# gnss.net
KiCad netlist of a schematic drawn in EAGLE
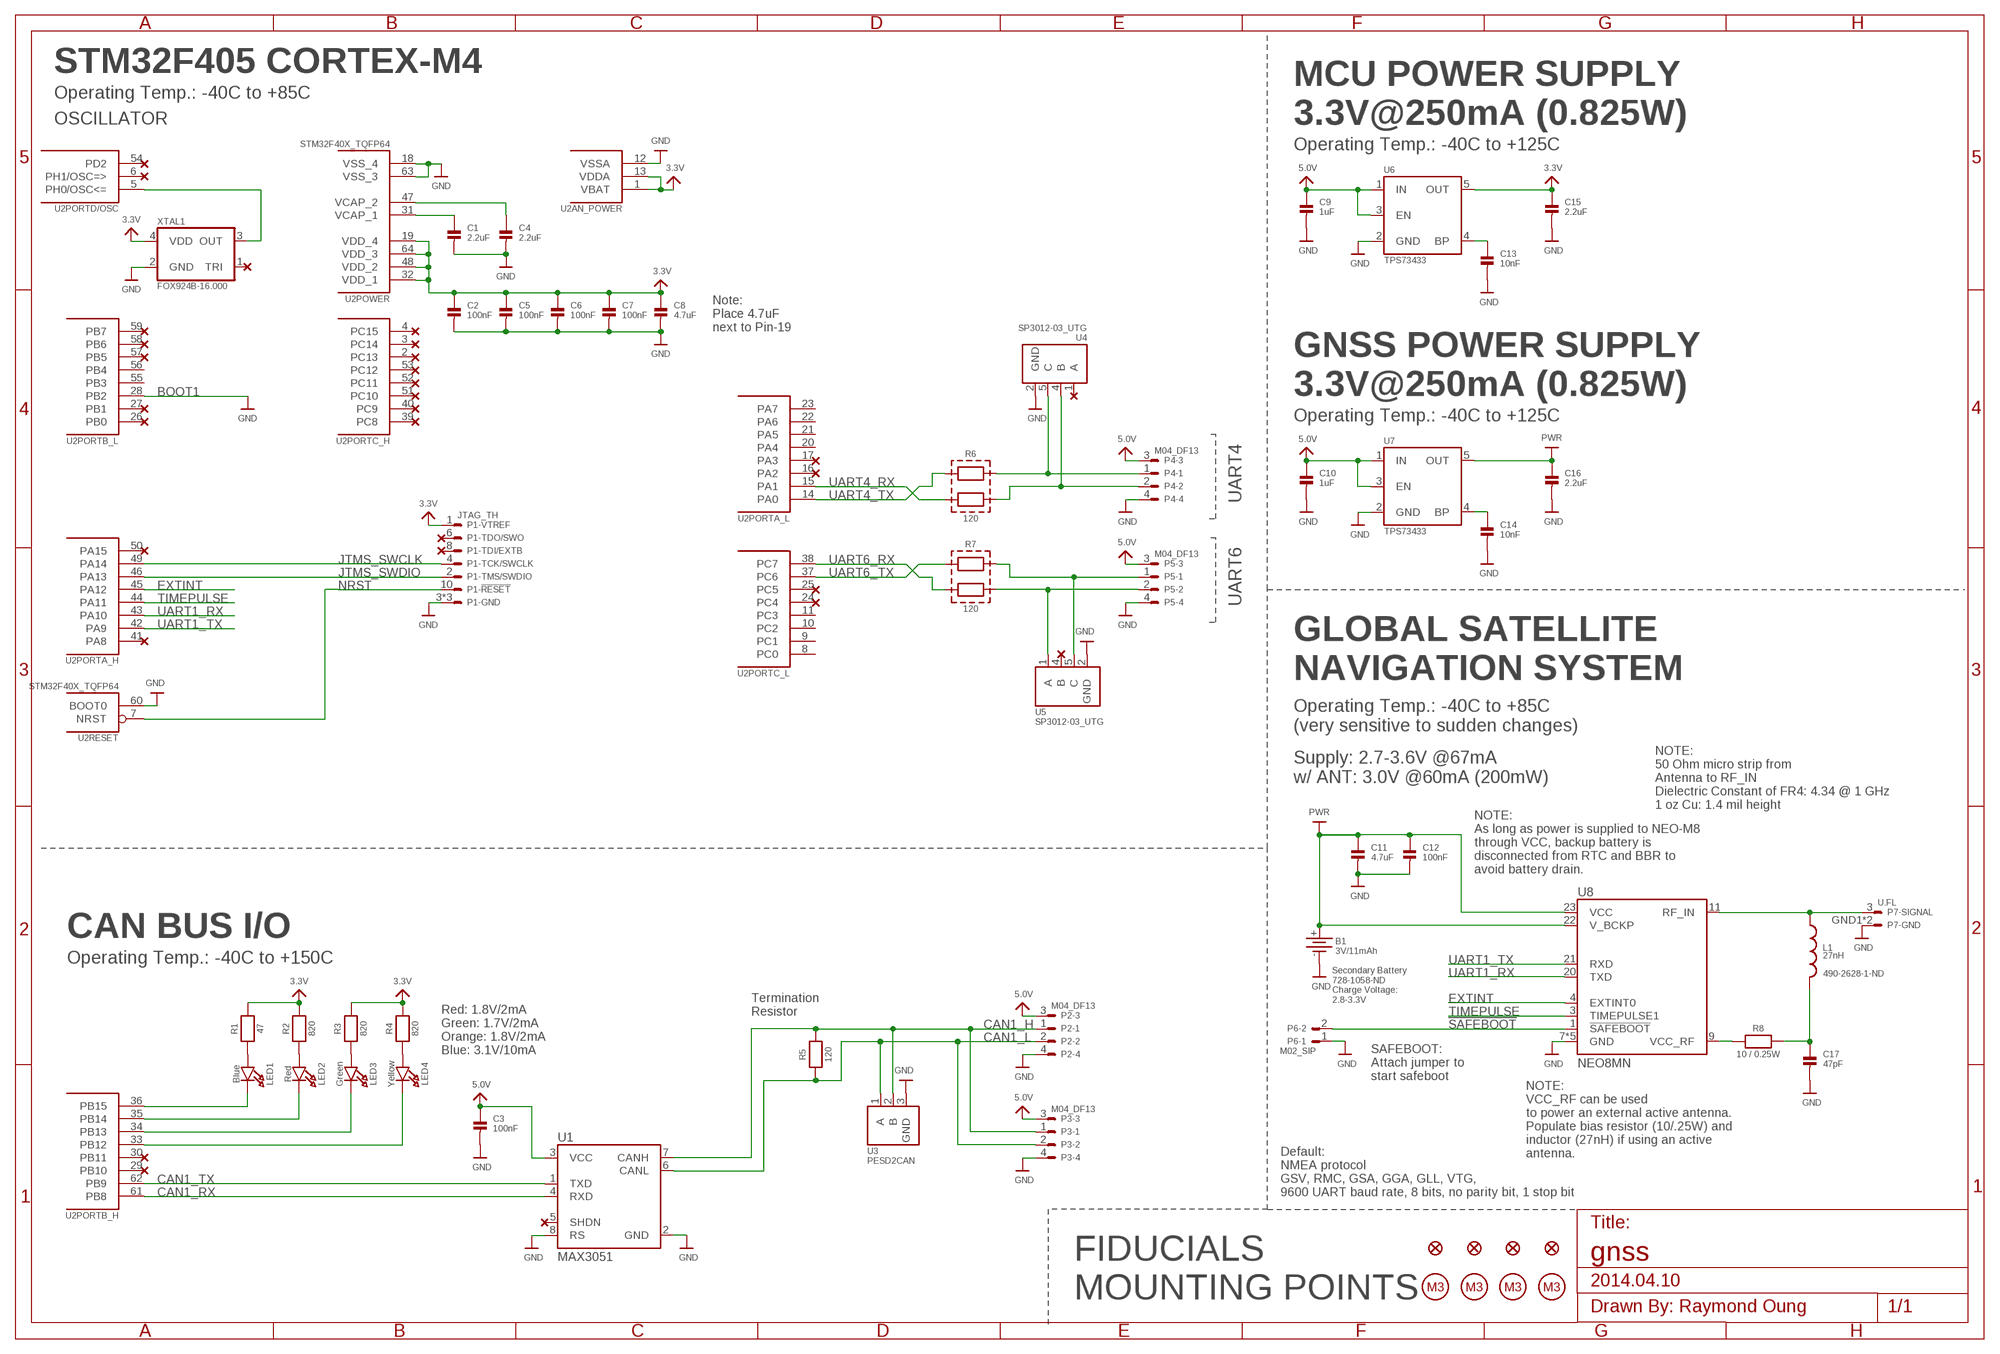
[diagram p0: schematic, sheet 1]

(export (version "E")
  (design (tool "Eeschema 10.0.6"))
  (components
    (comp (ref "B1")
      (value "3V/11mAh")
      (footprint "eagle-import:MS920SE")
      (libsource (lib "eagle-import") (part "BATTERY_MS920SE"))
    )
    (comp (ref "C1")
      (value "2.2uF")
      (footprint "eagle-import:0402")
      (libsource (lib "eagle-import") (part "CAP_CERAMIC0402"))
    )
    (comp (ref "C2")
      (value "100nF")
      (footprint "eagle-import:0402")
      (libsource (lib "eagle-import") (part "CAP_CERAMIC0402"))
    )
    (comp (ref "C3")
      (value "100nF")
      (footprint "eagle-import:0402")
      (libsource (lib "eagle-import") (part "CAP_CERAMIC0402"))
    )
    (comp (ref "C4")
      (value "2.2uF")
      (footprint "eagle-import:0402")
      (libsource (lib "eagle-import") (part "CAP_CERAMIC0402"))
    )
    (comp (ref "C5")
      (value "100nF")
      (footprint "eagle-import:0402")
      (libsource (lib "eagle-import") (part "CAP_CERAMIC0402"))
    )
    (comp (ref "C6")
      (value "100nF")
      (footprint "eagle-import:0402")
      (libsource (lib "eagle-import") (part "CAP_CERAMIC0402"))
    )
    (comp (ref "C7")
      (value "100nF")
      (footprint "eagle-import:0402")
      (libsource (lib "eagle-import") (part "CAP_CERAMIC0402"))
    )
    (comp (ref "C8")
      (value "4.7uF")
      (footprint "eagle-import:0402")
      (libsource (lib "eagle-import") (part "CAP_CERAMIC0402"))
    )
    (comp (ref "C9")
      (value "1uF")
      (footprint "eagle-import:0402")
      (libsource (lib "eagle-import") (part "CAP_CERAMIC0402"))
    )
    (comp (ref "C10")
      (value "1uF")
      (footprint "eagle-import:0402")
      (libsource (lib "eagle-import") (part "CAP_CERAMIC0402"))
    )
    (comp (ref "C11")
      (value "4.7uF")
      (footprint "eagle-import:0402")
      (libsource (lib "eagle-import") (part "CAP_CERAMIC0402"))
    )
    (comp (ref "C12")
      (value "100nF")
      (footprint "eagle-import:0402")
      (libsource (lib "eagle-import") (part "CAP_CERAMIC0402"))
    )
    (comp (ref "C13")
      (value "10nF")
      (footprint "eagle-import:0402")
      (libsource (lib "eagle-import") (part "CAP_CERAMIC0402"))
    )
    (comp (ref "C14")
      (value "10nF")
      (footprint "eagle-import:0402")
      (libsource (lib "eagle-import") (part "CAP_CERAMIC0402"))
    )
    (comp (ref "C15")
      (value "2.2uF")
      (footprint "eagle-import:0402")
      (libsource (lib "eagle-import") (part "CAP_CERAMIC0402"))
    )
    (comp (ref "C16")
      (value "2.2uF")
      (footprint "eagle-import:0402")
      (libsource (lib "eagle-import") (part "CAP_CERAMIC0402"))
    )
    (comp (ref "C17")
      (value "47pF")
      (footprint "eagle-import:0402")
      (libsource (lib "eagle-import") (part "CAP_CERAMIC0402"))
    )
    (comp (ref "L1")
      (value "27nH")
      (footprint "eagle-import:L0402")
      (libsource (lib "eagle-import") (part "INDUCTOR_0402"))
    )
    (comp (ref "LED1")
      (value "Blue")
      (footprint "eagle-import:CHIPLED_0603")
      (libsource (lib "eagle-import") (part "LED_0603"))
    )
    (comp (ref "LED2")
      (value "Red")
      (footprint "eagle-import:CHIPLED_0603")
      (libsource (lib "eagle-import") (part "LED_0603"))
    )
    (comp (ref "LED3")
      (value "Green")
      (footprint "eagle-import:CHIPLED_0603")
      (libsource (lib "eagle-import") (part "LED_0603"))
    )
    (comp (ref "LED4")
      (value "Yellow")
      (footprint "eagle-import:CHIPLED_0603")
      (libsource (lib "eagle-import") (part "LED_0603"))
    )
    (comp (ref "MP1")
      (value "M3")
      (footprint "eagle-import:MP_M3")
      (libsource (lib "eagle-import") (part "M3"))
    )
    (comp (ref "MP2")
      (value "M3")
      (footprint "eagle-import:MP_M3")
      (libsource (lib "eagle-import") (part "M3"))
    )
    (comp (ref "MP3")
      (value "M3")
      (footprint "eagle-import:MP_M3")
      (libsource (lib "eagle-import") (part "M3"))
    )
    (comp (ref "MP4")
      (value "M3")
      (footprint "eagle-import:MP_M3")
      (libsource (lib "eagle-import") (part "M3"))
    )
    (comp (ref "P1")
      (value "JTAG_TH")
      (footprint "eagle-import:FTSH-105-01-XXX-DV")
      (libsource (lib "eagle-import") (part "JTAG_TH"))
    )
    (comp (ref "P2")
      (value "M04_DF13")
      (footprint "eagle-import:DF13A-4P-1.25H")
      (libsource (lib "eagle-import") (part "M04_DF13"))
    )
    (comp (ref "P3")
      (value "M04_DF13")
      (footprint "eagle-import:DF13A-4P-1.25H")
      (libsource (lib "eagle-import") (part "M04_DF13"))
    )
    (comp (ref "P4")
      (value "M04_DF13")
      (footprint "eagle-import:DF13A-4P-1.25H")
      (libsource (lib "eagle-import") (part "M04_DF13"))
    )
    (comp (ref "P5")
      (value "M04_DF13")
      (footprint "eagle-import:DF13A-4P-1.25H")
      (libsource (lib "eagle-import") (part "M04_DF13"))
    )
    (comp (ref "P6")
      (value "M02_SIP")
      (footprint "eagle-import:1X02_LOCK")
      (libsource (lib "eagle-import") (part "M02_SIP"))
    )
    (comp (ref "P7")
      (value "U.FL")
      (footprint "eagle-import:U.FL")
      (libsource (lib "eagle-import") (part "U.FL"))
    )
    (comp (ref "R1")
      (value "47")
      (footprint "eagle-import:0402")
      (libsource (lib "eagle-import") (part "RESISTOR0402"))
    )
    (comp (ref "R2")
      (value "820")
      (footprint "eagle-import:0402")
      (libsource (lib "eagle-import") (part "RESISTOR0402"))
    )
    (comp (ref "R3")
      (value "820")
      (footprint "eagle-import:0402")
      (libsource (lib "eagle-import") (part "RESISTOR0402"))
    )
    (comp (ref "R4")
      (value "820")
      (footprint "eagle-import:0402")
      (libsource (lib "eagle-import") (part "RESISTOR0402"))
    )
    (comp (ref "R5")
      (value "120")
      (footprint "eagle-import:0603")
      (libsource (lib "eagle-import") (part "RESISTOR0603"))
    )
    (comp (ref "R6")
      (value "120")
      (footprint "eagle-import:EXBV4V")
      (libsource (lib "eagle-import") (part "RESISTOR2_0603X2"))
    )
    (comp (ref "R7")
      (value "120")
      (footprint "eagle-import:EXBV4V")
      (libsource (lib "eagle-import") (part "RESISTOR2_0603X2"))
    )
    (comp (ref "R8")
      (value "10 / 0.25W")
      (footprint "eagle-import:0603")
      (libsource (lib "eagle-import") (part "RESISTOR0603"))
    )
    (comp (ref "REF1")
      (value "FIDUCIAL1X2.5")
      (footprint "eagle-import:POINT-1MM")
      (libsource (lib "eagle-import") (part "FIDUCIAL1X2.5"))
    )
    (comp (ref "REF2")
      (value "FIDUCIAL1X2.5")
      (footprint "eagle-import:POINT-1MM")
      (libsource (lib "eagle-import") (part "FIDUCIAL1X2.5"))
    )
    (comp (ref "REF3")
      (value "FIDUCIAL1X2.5")
      (footprint "eagle-import:POINT-1MM")
      (libsource (lib "eagle-import") (part "FIDUCIAL1X2.5"))
    )
    (comp (ref "REF4")
      (value "FIDUCIAL1X2.5")
      (footprint "eagle-import:POINT-1MM")
      (libsource (lib "eagle-import") (part "FIDUCIAL1X2.5"))
    )
    (comp (ref "U1")
      (value "MAX3051")
      (footprint "eagle-import:SOT23-8")
      (libsource (lib "eagle-import") (part "MAX3051"))
    )
    (comp (ref "U2")
      (value "STM32F40X_TQFP64")
      (footprint "eagle-import:TQFP64")
      (libsource (lib "eagle-import") (part "STM32F40X_TQFP64"))
    )
    (comp (ref "U3")
      (value "PESD2CAN")
      (footprint "eagle-import:SOT23-3")
      (libsource (lib "eagle-import") (part "PESD2CAN"))
    )
    (comp (ref "U4")
      (value "SP3012-03_UTG")
      (footprint "eagle-import:UDFN06")
      (libsource (lib "eagle-import") (part "SP3012-03_UTG"))
    )
    (comp (ref "U5")
      (value "SP3012-03_UTG")
      (footprint "eagle-import:UDFN06")
      (libsource (lib "eagle-import") (part "SP3012-03_UTG"))
    )
    (comp (ref "U6")
      (value "TPS73433")
      (footprint "eagle-import:SOT23-5")
      (libsource (lib "eagle-import") (part "TPS73433"))
    )
    (comp (ref "U7")
      (value "TPS73433")
      (footprint "eagle-import:SOT23-5")
      (libsource (lib "eagle-import") (part "TPS73433"))
    )
    (comp (ref "U8")
      (value "NEO8MN")
      (footprint "eagle-import:NEOX")
      (libsource (lib "eagle-import") (part "NEO8MN"))
    )
    (comp (ref "XTAL1")
      (value "FOX924B-16.000")
      (footprint "eagle-import:OSCILLATOR-5.0X3.2A")
      (libsource (lib "eagle-import") (part "TCXO_5.0X3.2A"))
    )
  )
  (nets
    (net (code "1") (name "/CAN1_H") (class "Default")
      (node (ref "P2") (pin "1") (pinfunction "S_1") (pintype "passive"))
      (node (ref "P3") (pin "1") (pinfunction "S_1") (pintype "passive"))
      (node (ref "R5") (pin "2") (pinfunction "2_2") (pintype "passive"))
      (node (ref "U1") (pin "7") (pinfunction "CANH_7") (pintype "bidirectional"))
      (node (ref "U3") (pin "2") (pinfunction "B_2") (pintype "bidirectional"))
    )
    (net (code "2") (name "/CAN1_L") (class "Default")
      (node (ref "P2") (pin "2") (pinfunction "S_2") (pintype "passive"))
      (node (ref "P3") (pin "2") (pinfunction "S_2") (pintype "passive"))
      (node (ref "R5") (pin "1") (pinfunction "1_1") (pintype "passive"))
      (node (ref "U1") (pin "6") (pinfunction "CANL_6") (pintype "bidirectional"))
      (node (ref "U3") (pin "1") (pinfunction "A_1") (pintype "bidirectional"))
    )
    (net (code "3") (name "/CAN1_RX") (class "Default")
      (node (ref "U1") (pin "4") (pinfunction "RXD_4") (pintype "bidirectional"))
      (node (ref "U2") (pin "61") (pinfunction "PB8_61") (pintype "bidirectional"))
    )
    (net (code "4") (name "/CAN1_TX") (class "Default")
      (node (ref "U1") (pin "1") (pinfunction "TXD_1") (pintype "bidirectional"))
      (node (ref "U2") (pin "62") (pinfunction "PB9_62") (pintype "bidirectional"))
    )
    (net (code "5") (name "/EXTINT") (class "Default")
      (node (ref "U2") (pin "45") (pinfunction "PA12_45") (pintype "bidirectional"))
      (node (ref "U8") (pin "4") (pinfunction "EXTINT0_4") (pintype "bidirectional"))
    )
    (net (code "6") (name "/JTMS_SWCLK") (class "Default")
      (node (ref "P1") (pin "4") (pinfunction "S_4") (pintype "passive"))
      (node (ref "U2") (pin "49") (pinfunction "PA14_49") (pintype "bidirectional"))
    )
    (net (code "7") (name "/JTMS_SWDIO") (class "Default")
      (node (ref "P1") (pin "2") (pinfunction "S_2") (pintype "passive"))
      (node (ref "U2") (pin "46") (pinfunction "PA13_46") (pintype "bidirectional"))
    )
    (net (code "8") (name "/NRST") (class "Default")
      (node (ref "P1") (pin "10") (pinfunction "S_10") (pintype "passive"))
      (node (ref "U2") (pin "7") (pinfunction "NRST_7") (pintype "input"))
    )
    (net (code "9") (name "/TIMEPULSE") (class "Default")
      (node (ref "U2") (pin "44") (pinfunction "PA11_44") (pintype "bidirectional"))
      (node (ref "U8") (pin "3") (pinfunction "TIMEPULSE1_3") (pintype "bidirectional"))
    )
    (net (code "10") (name "/UART1_RX") (class "Default")
      (node (ref "U2") (pin "43") (pinfunction "PA10_43") (pintype "bidirectional"))
      (node (ref "U8") (pin "20") (pinfunction "TXD_20") (pintype "bidirectional"))
    )
    (net (code "11") (name "/UART1_TX") (class "Default")
      (node (ref "U2") (pin "42") (pinfunction "PA9_42") (pintype "bidirectional"))
      (node (ref "U8") (pin "21") (pinfunction "RXD_21") (pintype "bidirectional"))
    )
    (net (code "12") (name "/UART4_RX") (class "Default")
      (node (ref "R6") (pin "2") (pinfunction "2_2") (pintype "passive"))
      (node (ref "U2") (pin "15") (pinfunction "PA1_15") (pintype "bidirectional"))
    )
    (net (code "13") (name "/UART4_TX") (class "Default")
      (node (ref "R6") (pin "1") (pinfunction "1_1") (pintype "passive"))
      (node (ref "U2") (pin "14") (pinfunction "PA0_14") (pintype "bidirectional"))
    )
    (net (code "14") (name "/UART6_RX") (class "Default")
      (node (ref "R7") (pin "2") (pinfunction "2_2") (pintype "passive"))
      (node (ref "U2") (pin "38") (pinfunction "PC7_38") (pintype "bidirectional"))
    )
    (net (code "15") (name "/UART6_TX") (class "Default")
      (node (ref "R7") (pin "1") (pinfunction "1_1") (pintype "passive"))
      (node (ref "U2") (pin "37") (pinfunction "PC6_37") (pintype "bidirectional"))
    )
    (net (code "16") (name "/~{SAFEBOOT}") (class "Default")
      (node (ref "P6") (pin "2") (pinfunction "S_2") (pintype "passive"))
      (node (ref "U8") (pin "1") (pinfunction "~{SAFEBOOT}_1") (pintype "bidirectional"))
    )
    (net (code "17") (name "3.3V") (class "Default")
      (node (ref "C15") (pin "1") (pinfunction "P$1_1") (pintype "passive"))
      (node (ref "C2") (pin "1") (pinfunction "P$1_1") (pintype "passive"))
      (node (ref "C5") (pin "1") (pinfunction "P$1_1") (pintype "passive"))
      (node (ref "C6") (pin "1") (pinfunction "P$1_1") (pintype "passive"))
      (node (ref "C7") (pin "1") (pinfunction "P$1_1") (pintype "passive"))
      (node (ref "C8") (pin "1") (pinfunction "P$1_1") (pintype "passive"))
      (node (ref "P1") (pin "1") (pinfunction "S_1") (pintype "passive"))
      (node (ref "R1") (pin "2") (pinfunction "2_2") (pintype "passive"))
      (node (ref "R2") (pin "2") (pinfunction "2_2") (pintype "passive"))
      (node (ref "R3") (pin "2") (pinfunction "2_2") (pintype "passive"))
      (node (ref "R4") (pin "2") (pinfunction "2_2") (pintype "passive"))
      (node (ref "U2") (pin "1") (pinfunction "VBAT_1") (pintype "power_in"))
      (node (ref "U2") (pin "13") (pinfunction "VDDA_13") (pintype "power_in"))
      (node (ref "U2") (pin "19") (pinfunction "VDD_4_19") (pintype "power_in"))
      (node (ref "U2") (pin "32") (pinfunction "VDD_1_32") (pintype "power_in"))
      (node (ref "U2") (pin "48") (pinfunction "VDD_2_48") (pintype "power_in"))
      (node (ref "U2") (pin "64") (pinfunction "VDD_3_64") (pintype "power_in"))
      (node (ref "U6") (pin "5") (pinfunction "OUT_5") (pintype "bidirectional"))
      (node (ref "XTAL1") (pin "4") (pinfunction "VDD_4") (pintype "bidirectional"))
    )
    (net (code "18") (name "5.0V") (class "Default")
      (node (ref "C10") (pin "1") (pinfunction "P$1_1") (pintype "passive"))
      (node (ref "C3") (pin "1") (pinfunction "P$1_1") (pintype "passive"))
      (node (ref "C9") (pin "1") (pinfunction "P$1_1") (pintype "passive"))
      (node (ref "P2") (pin "3") (pinfunction "S_3") (pintype "passive"))
      (node (ref "P3") (pin "3") (pinfunction "S_3") (pintype "passive"))
      (node (ref "P4") (pin "3") (pinfunction "S_3") (pintype "passive"))
      (node (ref "P5") (pin "3") (pinfunction "S_3") (pintype "passive"))
      (node (ref "U1") (pin "3") (pinfunction "VCC_3") (pintype "bidirectional"))
      (node (ref "U6") (pin "1") (pinfunction "IN_1") (pintype "bidirectional"))
      (node (ref "U6") (pin "3") (pinfunction "EN_3") (pintype "bidirectional"))
      (node (ref "U7") (pin "1") (pinfunction "IN_1") (pintype "bidirectional"))
      (node (ref "U7") (pin "3") (pinfunction "EN_3") (pintype "bidirectional"))
    )
    (net (code "19") (name "GND") (class "Default")
      (node (ref "B1") (pin "-") (pinfunction "-_-") (pintype "bidirectional"))
      (node (ref "C1") (pin "2") (pinfunction "P$2_2") (pintype "passive"))
      (node (ref "C10") (pin "2") (pinfunction "P$2_2") (pintype "passive"))
      (node (ref "C11") (pin "2") (pinfunction "P$2_2") (pintype "passive"))
      (node (ref "C12") (pin "2") (pinfunction "P$2_2") (pintype "passive"))
      (node (ref "C13") (pin "2") (pinfunction "P$2_2") (pintype "passive"))
      (node (ref "C14") (pin "2") (pinfunction "P$2_2") (pintype "passive"))
      (node (ref "C15") (pin "2") (pinfunction "P$2_2") (pintype "passive"))
      (node (ref "C16") (pin "2") (pinfunction "P$2_2") (pintype "passive"))
      (node (ref "C17") (pin "2") (pinfunction "P$2_2") (pintype "passive"))
      (node (ref "C2") (pin "2") (pinfunction "P$2_2") (pintype "passive"))
      (node (ref "C3") (pin "2") (pinfunction "P$2_2") (pintype "passive"))
      (node (ref "C4") (pin "2") (pinfunction "P$2_2") (pintype "passive"))
      (node (ref "C5") (pin "2") (pinfunction "P$2_2") (pintype "passive"))
      (node (ref "C6") (pin "2") (pinfunction "P$2_2") (pintype "passive"))
      (node (ref "C7") (pin "2") (pinfunction "P$2_2") (pintype "passive"))
      (node (ref "C8") (pin "2") (pinfunction "P$2_2") (pintype "passive"))
      (node (ref "C9") (pin "2") (pinfunction "P$2_2") (pintype "passive"))
      (node (ref "P1") (pin "3") (pinfunction "S_3") (pintype "passive"))
      (node (ref "P1") (pin "5") (pinfunction "S_5") (pintype "passive"))
      (node (ref "P1") (pin "9") (pinfunction "S_9") (pintype "passive"))
      (node (ref "P2") (pin "4") (pinfunction "S_4") (pintype "passive"))
      (node (ref "P3") (pin "4") (pinfunction "S_4") (pintype "passive"))
      (node (ref "P4") (pin "4") (pinfunction "S_4") (pintype "passive"))
      (node (ref "P5") (pin "4") (pinfunction "S_4") (pintype "passive"))
      (node (ref "P6") (pin "1") (pinfunction "S_1") (pintype "passive"))
      (node (ref "P7") (pin "GND1") (pinfunction "S_GND1") (pintype "passive"))
      (node (ref "P7") (pin "GND2") (pinfunction "S_GND2") (pintype "passive"))
      (node (ref "U1") (pin "2") (pinfunction "GND_2") (pintype "bidirectional"))
      (node (ref "U1") (pin "8") (pinfunction "RS_8") (pintype "bidirectional"))
      (node (ref "U2") (pin "12") (pinfunction "VSSA_12") (pintype "power_in"))
      (node (ref "U2") (pin "18") (pinfunction "VSS_4_18") (pintype "power_in"))
      (node (ref "U2") (pin "28") (pinfunction "PB2_28") (pintype "bidirectional"))
      (node (ref "U2") (pin "60") (pinfunction "BOOT0_60") (pintype "input"))
      (node (ref "U2") (pin "63") (pinfunction "VSS_3_63") (pintype "power_in"))
      (node (ref "U3") (pin "3") (pinfunction "GND_3") (pintype "power_in"))
      (node (ref "U4") (pin "2") (pinfunction "GND_2") (pintype "power_in"))
      (node (ref "U5") (pin "2") (pinfunction "GND_2") (pintype "power_in"))
      (node (ref "U6") (pin "2") (pinfunction "GND_2") (pintype "bidirectional"))
      (node (ref "U7") (pin "2") (pinfunction "GND_2") (pintype "bidirectional"))
      (node (ref "U8") (pin "10") (pinfunction "GND_10") (pintype "bidirectional"))
      (node (ref "U8") (pin "12") (pinfunction "GND_12") (pintype "bidirectional"))
      (node (ref "U8") (pin "13") (pinfunction "GND_13") (pintype "bidirectional"))
      (node (ref "U8") (pin "24") (pinfunction "GND_24") (pintype "bidirectional"))
      (node (ref "U8") (pin "7") (pinfunction "GND_7") (pintype "bidirectional"))
      (node (ref "XTAL1") (pin "2") (pinfunction "GND_2") (pintype "bidirectional"))
    )
    (net (code "20") (name "Net-(C1-P$1)") (class "Default")
      (node (ref "C1") (pin "1") (pinfunction "P$1_1") (pintype "passive"))
      (node (ref "U2") (pin "31") (pinfunction "VCAP_1_31") (pintype "power_in"))
    )
    (net (code "21") (name "Net-(C4-P$1)") (class "Default")
      (node (ref "C4") (pin "1") (pinfunction "P$1_1") (pintype "passive"))
      (node (ref "U2") (pin "47") (pinfunction "VCAP_2_47") (pintype "power_in"))
    )
    (net (code "22") (name "Net-(C13-P$1)") (class "Default")
      (node (ref "C13") (pin "1") (pinfunction "P$1_1") (pintype "passive"))
      (node (ref "U6") (pin "4") (pinfunction "BP_4") (pintype "bidirectional"))
    )
    (net (code "23") (name "Net-(C14-P$1)") (class "Default")
      (node (ref "C14") (pin "1") (pinfunction "P$1_1") (pintype "passive"))
      (node (ref "U7") (pin "4") (pinfunction "BP_4") (pintype "bidirectional"))
    )
    (net (code "24") (name "Net-(C17-P$1)") (class "Default")
      (node (ref "C17") (pin "1") (pinfunction "P$1_1") (pintype "passive"))
      (node (ref "L1") (pin "2") (pinfunction "2_2") (pintype "passive"))
      (node (ref "R8") (pin "2") (pinfunction "2_2") (pintype "passive"))
    )
    (net (code "25") (name "Net-(LED1-PadA)") (class "Default")
      (node (ref "LED1") (pin "A") (pinfunction "A_A") (pintype "passive"))
      (node (ref "R1") (pin "1") (pinfunction "1_1") (pintype "passive"))
    )
    (net (code "26") (name "Net-(LED2-PadA)") (class "Default")
      (node (ref "LED2") (pin "A") (pinfunction "A_A") (pintype "passive"))
      (node (ref "R2") (pin "1") (pinfunction "1_1") (pintype "passive"))
    )
    (net (code "27") (name "Net-(LED3-PadA)") (class "Default")
      (node (ref "LED3") (pin "A") (pinfunction "A_A") (pintype "passive"))
      (node (ref "R3") (pin "1") (pinfunction "1_1") (pintype "passive"))
    )
    (net (code "28") (name "Net-(LED4-PadA)") (class "Default")
      (node (ref "LED4") (pin "A") (pinfunction "A_A") (pintype "passive"))
      (node (ref "R4") (pin "1") (pinfunction "1_1") (pintype "passive"))
    )
    (net (code "29") (name "Net-(P4A-S)") (class "Default")
      (node (ref "P4") (pin "1") (pinfunction "S_1") (pintype "passive"))
      (node (ref "R6") (pin "4") (pinfunction "4_4") (pintype "passive"))
      (node (ref "U4") (pin "5") (pinfunction "C_5") (pintype "bidirectional"))
    )
    (net (code "30") (name "Net-(P4B-S)") (class "Default")
      (node (ref "P4") (pin "2") (pinfunction "S_2") (pintype "passive"))
      (node (ref "R6") (pin "3") (pinfunction "3_3") (pintype "passive"))
      (node (ref "U4") (pin "4") (pinfunction "B_4") (pintype "bidirectional"))
    )
    (net (code "31") (name "Net-(P5A-S)") (class "Default")
      (node (ref "P5") (pin "1") (pinfunction "S_1") (pintype "passive"))
      (node (ref "R7") (pin "4") (pinfunction "4_4") (pintype "passive"))
      (node (ref "U5") (pin "5") (pinfunction "C_5") (pintype "bidirectional"))
    )
    (net (code "32") (name "Net-(P5B-S)") (class "Default")
      (node (ref "P5") (pin "2") (pinfunction "S_2") (pintype "passive"))
      (node (ref "R7") (pin "3") (pinfunction "3_3") (pintype "passive"))
      (node (ref "U5") (pin "1") (pinfunction "A_1") (pintype "bidirectional"))
    )
    (net (code "33") (name "Net-(P7B-S)") (class "Default")
      (node (ref "L1") (pin "1") (pinfunction "1_1") (pintype "passive"))
      (node (ref "P7") (pin "3") (pinfunction "S_3") (pintype "passive"))
      (node (ref "U8") (pin "11") (pinfunction "RF_IN_11") (pintype "bidirectional"))
    )
    (net (code "34") (name "Net-(U2D-PB12)") (class "Default")
      (node (ref "LED4") (pin "C") (pinfunction "C_C") (pintype "passive"))
      (node (ref "U2") (pin "33") (pinfunction "PB12_33") (pintype "bidirectional"))
    )
    (net (code "35") (name "Net-(U2D-PB13)") (class "Default")
      (node (ref "LED3") (pin "C") (pinfunction "C_C") (pintype "passive"))
      (node (ref "U2") (pin "34") (pinfunction "PB13_34") (pintype "bidirectional"))
    )
    (net (code "36") (name "Net-(U2D-PB14)") (class "Default")
      (node (ref "LED2") (pin "C") (pinfunction "C_C") (pintype "passive"))
      (node (ref "U2") (pin "35") (pinfunction "PB14_35") (pintype "bidirectional"))
    )
    (net (code "37") (name "Net-(U2D-PB15)") (class "Default")
      (node (ref "LED1") (pin "C") (pinfunction "C_C") (pintype "passive"))
      (node (ref "U2") (pin "36") (pinfunction "PB15_36") (pintype "bidirectional"))
    )
    (net (code "38") (name "Net-(U2H-PH0{slash}OSC<=)") (class "Default")
      (node (ref "U2") (pin "5") (pinfunction "PH0/OSC<=_5") (pintype "bidirectional"))
      (node (ref "XTAL1") (pin "3") (pinfunction "OUT_3") (pintype "bidirectional"))
    )
    (net (code "39") (name "Net-(U8-VCC_RF)") (class "Default")
      (node (ref "R8") (pin "1") (pinfunction "1_1") (pintype "passive"))
      (node (ref "U8") (pin "9") (pinfunction "VCC_RF_9") (pintype "bidirectional"))
    )
    (net (code "40") (name "PWR") (class "Default")
      (node (ref "B1") (pin "+") (pinfunction "+_+") (pintype "bidirectional"))
      (node (ref "C11") (pin "1") (pinfunction "P$1_1") (pintype "passive"))
      (node (ref "C12") (pin "1") (pinfunction "P$1_1") (pintype "passive"))
      (node (ref "C16") (pin "1") (pinfunction "P$1_1") (pintype "passive"))
      (node (ref "U7") (pin "5") (pinfunction "OUT_5") (pintype "bidirectional"))
      (node (ref "U8") (pin "22") (pinfunction "V_BCKP_22") (pintype "power_in"))
      (node (ref "U8") (pin "23") (pinfunction "VCC_23") (pintype "power_in"))
    )
    (net (code "41") (name "unconnected-(P1D-S-Pad8)") (class "Default")
      (node (ref "P1") (pin "8") (pinfunction "S_8") (pintype "passive"))
    )
    (net (code "42") (name "unconnected-(P1E-S-Pad6)") (class "Default")
      (node (ref "P1") (pin "6") (pinfunction "S_6") (pintype "passive"))
    )
    (net (code "43") (name "unconnected-(U1-SHDN-Pad5)") (class "Default")
      (node (ref "U1") (pin "5") (pinfunction "SHDN_5") (pintype "bidirectional"))
    )
    (net (code "44") (name "unconnected-(U2B-PA8-Pad41)") (class "Default")
      (node (ref "U2") (pin "41") (pinfunction "PA8_41") (pintype "bidirectional"))
    )
    (net (code "45") (name "unconnected-(U2B-PA15-Pad50)") (class "Default")
      (node (ref "U2") (pin "50") (pinfunction "PA15_50") (pintype "bidirectional"))
    )
    (net (code "46") (name "unconnected-(U2C-PA2-Pad16)") (class "Default")
      (node (ref "U2") (pin "16") (pinfunction "PA2_16") (pintype "bidirectional"))
    )
    (net (code "47") (name "unconnected-(U2C-PA3-Pad17)") (class "Default")
      (node (ref "U2") (pin "17") (pinfunction "PA3_17") (pintype "bidirectional"))
    )
    (net (code "48") (name "unconnected-(U2C-PA4-Pad20)") (class "Default")
      (node (ref "U2") (pin "20") (pinfunction "PA4_20") (pintype "bidirectional"))
    )
    (net (code "49") (name "unconnected-(U2C-PA5-Pad21)") (class "Default")
      (node (ref "U2") (pin "21") (pinfunction "PA5_21") (pintype "bidirectional"))
    )
    (net (code "50") (name "unconnected-(U2C-PA6-Pad22)") (class "Default")
      (node (ref "U2") (pin "22") (pinfunction "PA6_22") (pintype "bidirectional"))
    )
    (net (code "51") (name "unconnected-(U2C-PA7-Pad23)") (class "Default")
      (node (ref "U2") (pin "23") (pinfunction "PA7_23") (pintype "bidirectional"))
    )
    (net (code "52") (name "unconnected-(U2D-PB10-Pad29)") (class "Default")
      (node (ref "U2") (pin "29") (pinfunction "PB10_29") (pintype "bidirectional"))
    )
    (net (code "53") (name "unconnected-(U2D-PB11-Pad30)") (class "Default")
      (node (ref "U2") (pin "30") (pinfunction "PB11_30") (pintype "bidirectional"))
    )
    (net (code "54") (name "unconnected-(U2E-PB0-Pad26)") (class "Default")
      (node (ref "U2") (pin "26") (pinfunction "PB0_26") (pintype "bidirectional"))
    )
    (net (code "55") (name "unconnected-(U2E-PB1-Pad27)") (class "Default")
      (node (ref "U2") (pin "27") (pinfunction "PB1_27") (pintype "bidirectional"))
    )
    (net (code "56") (name "unconnected-(U2E-PB3-Pad55)") (class "Default")
      (node (ref "U2") (pin "55") (pinfunction "PB3_55") (pintype "bidirectional"))
    )
    (net (code "57") (name "unconnected-(U2E-PB4-Pad56)") (class "Default")
      (node (ref "U2") (pin "56") (pinfunction "PB4_56") (pintype "bidirectional"))
    )
    (net (code "58") (name "unconnected-(U2E-PB5-Pad57)") (class "Default")
      (node (ref "U2") (pin "57") (pinfunction "PB5_57") (pintype "bidirectional"))
    )
    (net (code "59") (name "unconnected-(U2E-PB6-Pad58)") (class "Default")
      (node (ref "U2") (pin "58") (pinfunction "PB6_58") (pintype "bidirectional"))
    )
    (net (code "60") (name "unconnected-(U2E-PB7-Pad59)") (class "Default")
      (node (ref "U2") (pin "59") (pinfunction "PB7_59") (pintype "bidirectional"))
    )
    (net (code "61") (name "unconnected-(U2F-PC8-Pad39)") (class "Default")
      (node (ref "U2") (pin "39") (pinfunction "PC8_39") (pintype "bidirectional"))
    )
    (net (code "62") (name "unconnected-(U2F-PC9-Pad40)") (class "Default")
      (node (ref "U2") (pin "40") (pinfunction "PC9_40") (pintype "bidirectional"))
    )
    (net (code "63") (name "unconnected-(U2F-PC10-Pad51)") (class "Default")
      (node (ref "U2") (pin "51") (pinfunction "PC10_51") (pintype "bidirectional"))
    )
    (net (code "64") (name "unconnected-(U2F-PC11-Pad52)") (class "Default")
      (node (ref "U2") (pin "52") (pinfunction "PC11_52") (pintype "bidirectional"))
    )
    (net (code "65") (name "unconnected-(U2F-PC12-Pad53)") (class "Default")
      (node (ref "U2") (pin "53") (pinfunction "PC12_53") (pintype "bidirectional"))
    )
    (net (code "66") (name "unconnected-(U2F-PC13-Pad2)") (class "Default")
      (node (ref "U2") (pin "2") (pinfunction "PC13_2") (pintype "bidirectional"))
    )
    (net (code "67") (name "unconnected-(U2F-PC14-Pad3)") (class "Default")
      (node (ref "U2") (pin "3") (pinfunction "PC14_3") (pintype "bidirectional"))
    )
    (net (code "68") (name "unconnected-(U2F-PC15-Pad4)") (class "Default")
      (node (ref "U2") (pin "4") (pinfunction "PC15_4") (pintype "bidirectional"))
    )
    (net (code "69") (name "unconnected-(U2G-PC0-Pad8)") (class "Default")
      (node (ref "U2") (pin "8") (pinfunction "PC0_8") (pintype "bidirectional"))
    )
    (net (code "70") (name "unconnected-(U2G-PC1-Pad9)") (class "Default")
      (node (ref "U2") (pin "9") (pinfunction "PC1_9") (pintype "bidirectional"))
    )
    (net (code "71") (name "unconnected-(U2G-PC2-Pad10)") (class "Default")
      (node (ref "U2") (pin "10") (pinfunction "PC2_10") (pintype "bidirectional"))
    )
    (net (code "72") (name "unconnected-(U2G-PC3-Pad11)") (class "Default")
      (node (ref "U2") (pin "11") (pinfunction "PC3_11") (pintype "bidirectional"))
    )
    (net (code "73") (name "unconnected-(U2G-PC4-Pad24)") (class "Default")
      (node (ref "U2") (pin "24") (pinfunction "PC4_24") (pintype "bidirectional"))
    )
    (net (code "74") (name "unconnected-(U2G-PC5-Pad25)") (class "Default")
      (node (ref "U2") (pin "25") (pinfunction "PC5_25") (pintype "bidirectional"))
    )
    (net (code "75") (name "unconnected-(U2H-PD2-Pad54)") (class "Default")
      (node (ref "U2") (pin "54") (pinfunction "PD2_54") (pintype "bidirectional"))
    )
    (net (code "76") (name "unconnected-(U2H-PH1{slash}OSC=>-Pad6)") (class "Default")
      (node (ref "U2") (pin "6") (pinfunction "PH1/OSC=>_6") (pintype "bidirectional"))
    )
    (net (code "77") (name "unconnected-(U4-A-Pad1)") (class "Default")
      (node (ref "U4") (pin "1") (pinfunction "A_1") (pintype "bidirectional"))
    )
    (net (code "78") (name "unconnected-(U5-B-Pad4)") (class "Default")
      (node (ref "U5") (pin "4") (pinfunction "B_4") (pintype "bidirectional"))
    )
    (net (code "79") (name "unconnected-(XTAL1-TRI-Pad1)") (class "Default")
      (node (ref "XTAL1") (pin "1") (pinfunction "TRI_1") (pintype "bidirectional"))
    )
  )
)
